# LED_Driver_BrkOut.net
KiCad netlist of a schematic drawn in EAGLE
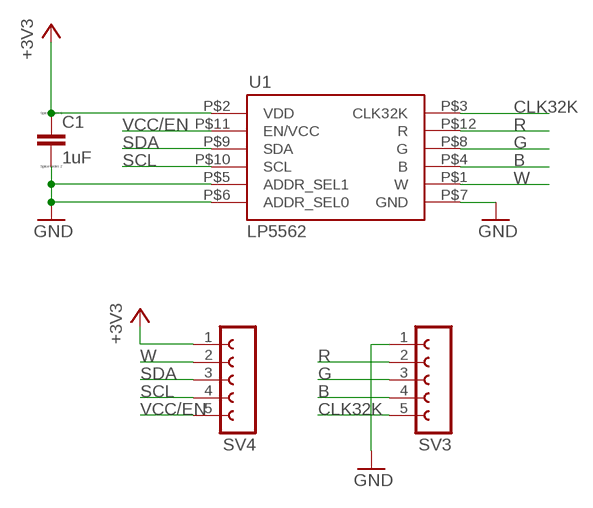
[diagram p0: schematic, sheet 1]

(export (version "E")
  (design (tool "Eeschema 10.0.6"))
  (components
    (comp (ref "C1")
      (value "1uF")
      (footprint "eagle-import:C0603")
      (libsource (lib "eagle-import") (part "CC0603"))
    )
    (comp (ref "SV3")
      (value "FE05-1")
      (footprint "eagle-import:FE05-1")
      (libsource (lib "eagle-import") (part "FE05-1"))
    )
    (comp (ref "SV4")
      (value "FE05-1")
      (footprint "eagle-import:FE05-1")
      (libsource (lib "eagle-import") (part "FE05-1"))
    )
    (comp (ref "U1")
      (value "LP5562")
      (footprint "eagle-import:YQE_12-PIN_DSBGA")
      (libsource (lib "eagle-import") (part "LP5562LP5562"))
    )
  )
  (nets
    (net (code "1") (name "+3V3") (class "Default")
      (node (ref "C1") (pin "1") (pinfunction "1_1") (pintype "passive"))
      (node (ref "SV4") (pin "1") (pinfunction "1_1") (pintype "passive"))
      (node (ref "U1") (pin "P$2") (pinfunction "VDD_P$2") (pintype "power_in"))
    )
    (net (code "2") (name "/B") (class "Default")
      (node (ref "SV3") (pin "4") (pinfunction "4_4") (pintype "passive"))
      (node (ref "U1") (pin "P$4") (pinfunction "B_P$4") (pintype "output"))
    )
    (net (code "3") (name "/CLK32K") (class "Default")
      (node (ref "SV3") (pin "5") (pinfunction "5_5") (pintype "passive"))
      (node (ref "U1") (pin "P$3") (pinfunction "CLK32K_P$3") (pintype "input"))
    )
    (net (code "4") (name "/G") (class "Default")
      (node (ref "SV3") (pin "3") (pinfunction "3_3") (pintype "passive"))
      (node (ref "U1") (pin "P$8") (pinfunction "G_P$8") (pintype "output"))
    )
    (net (code "5") (name "/R") (class "Default")
      (node (ref "SV3") (pin "2") (pinfunction "2_2") (pintype "passive"))
      (node (ref "U1") (pin "P$12") (pinfunction "R_P$12") (pintype "output"))
    )
    (net (code "6") (name "/SCL") (class "Default")
      (node (ref "SV4") (pin "4") (pinfunction "4_4") (pintype "passive"))
      (node (ref "U1") (pin "P$10") (pinfunction "SCL_P$10") (pintype "bidirectional"))
    )
    (net (code "7") (name "/SDA") (class "Default")
      (node (ref "SV4") (pin "3") (pinfunction "3_3") (pintype "passive"))
      (node (ref "U1") (pin "P$9") (pinfunction "SDA_P$9") (pintype "bidirectional"))
    )
    (net (code "8") (name "/VCC{slash}EN") (class "Default")
      (node (ref "SV4") (pin "5") (pinfunction "5_5") (pintype "passive"))
      (node (ref "U1") (pin "P$11") (pinfunction "EN/VCC_P$11") (pintype "input"))
    )
    (net (code "9") (name "/W") (class "Default")
      (node (ref "SV4") (pin "2") (pinfunction "2_2") (pintype "passive"))
      (node (ref "U1") (pin "P$1") (pinfunction "W_P$1") (pintype "output"))
    )
    (net (code "10") (name "GND") (class "Default")
      (node (ref "C1") (pin "2") (pinfunction "2_2") (pintype "passive"))
      (node (ref "SV3") (pin "1") (pinfunction "1_1") (pintype "passive"))
      (node (ref "U1") (pin "P$5") (pinfunction "ADDR_SEL1_P$5") (pintype "input"))
      (node (ref "U1") (pin "P$6") (pinfunction "ADDR_SEL0_P$6") (pintype "input"))
      (node (ref "U1") (pin "P$7") (pinfunction "GND_P$7") (pintype "power_in"))
    )
  )
)
